# Connectors.net
KiCad netlist of a schematic drawn in Altium Designer
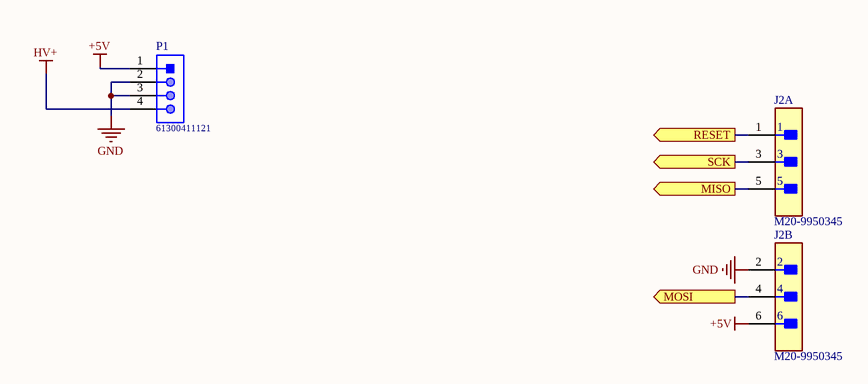
[diagram p0: Connectors.SchDoc]

(export (version "E")
  (design (tool "Eeschema 10.0.6"))
  (components
    (comp (ref "J2")
      (value "M20-9950345")
      (footprint "FP-M20-9950345-MFG")
      (description "CONN HEADER R/A 6POS 2.54MM")
      (fields
        (field (name "OCTOPART") "https://octopart.com/m20-9950345-harwin-21265213")
        (field (name "MANUFACTURER") "Harwin")
      )
      (libsource (lib "Altium Content Vault") (part "b76336891f9c52daa0497ceff74f613"))
    )
    (comp (ref "P1")
      (value "61300411121")
      (footprint "61300411121")
      (description "THT Vertical Pin Header WR-PHD, Pitch 2.54 mm, Single Row, 4 pins")
      (fields (field (name "MANUFACTURER") "Wurth Elektronik") (field (name "PUBLISHER") "WurthElektronik"))
      (libsource (lib "Altium Content Vault") (part "WE-CN-1P-M-R4"))
    )
  )
  (nets
    (net (code "1") (name "+5V") (class "Default")
      (node (ref "J2") (pin "6") (pinfunction "6_6") (pintype "passive"))
      (node (ref "P1") (pin "1") (pinfunction "1_1") (pintype "passive"))
    )
    (net (code "2") (name "/MISO") (class "Default")
      (node (ref "J2") (pin "5") (pinfunction "5_5") (pintype "passive"))
    )
    (net (code "3") (name "/MOSI") (class "Default")
      (node (ref "J2") (pin "4") (pinfunction "4_4") (pintype "passive"))
    )
    (net (code "4") (name "/RESET") (class "Default")
      (node (ref "J2") (pin "1") (pinfunction "1_1") (pintype "passive"))
    )
    (net (code "5") (name "/SCK") (class "Default")
      (node (ref "J2") (pin "3") (pinfunction "3_3") (pintype "passive"))
    )
    (net (code "6") (name "GND") (class "Default")
      (node (ref "J2") (pin "2") (pinfunction "2_2") (pintype "passive"))
      (node (ref "P1") (pin "2") (pinfunction "2_2") (pintype "passive"))
      (node (ref "P1") (pin "3") (pinfunction "3_3") (pintype "passive"))
    )
    (net (code "7") (name "HV+") (class "Default")
      (node (ref "P1") (pin "4") (pinfunction "4_4") (pintype "passive"))
    )
  )
)
